# Sheet2-USB.net
KiCad netlist of a schematic drawn in Altium Designer
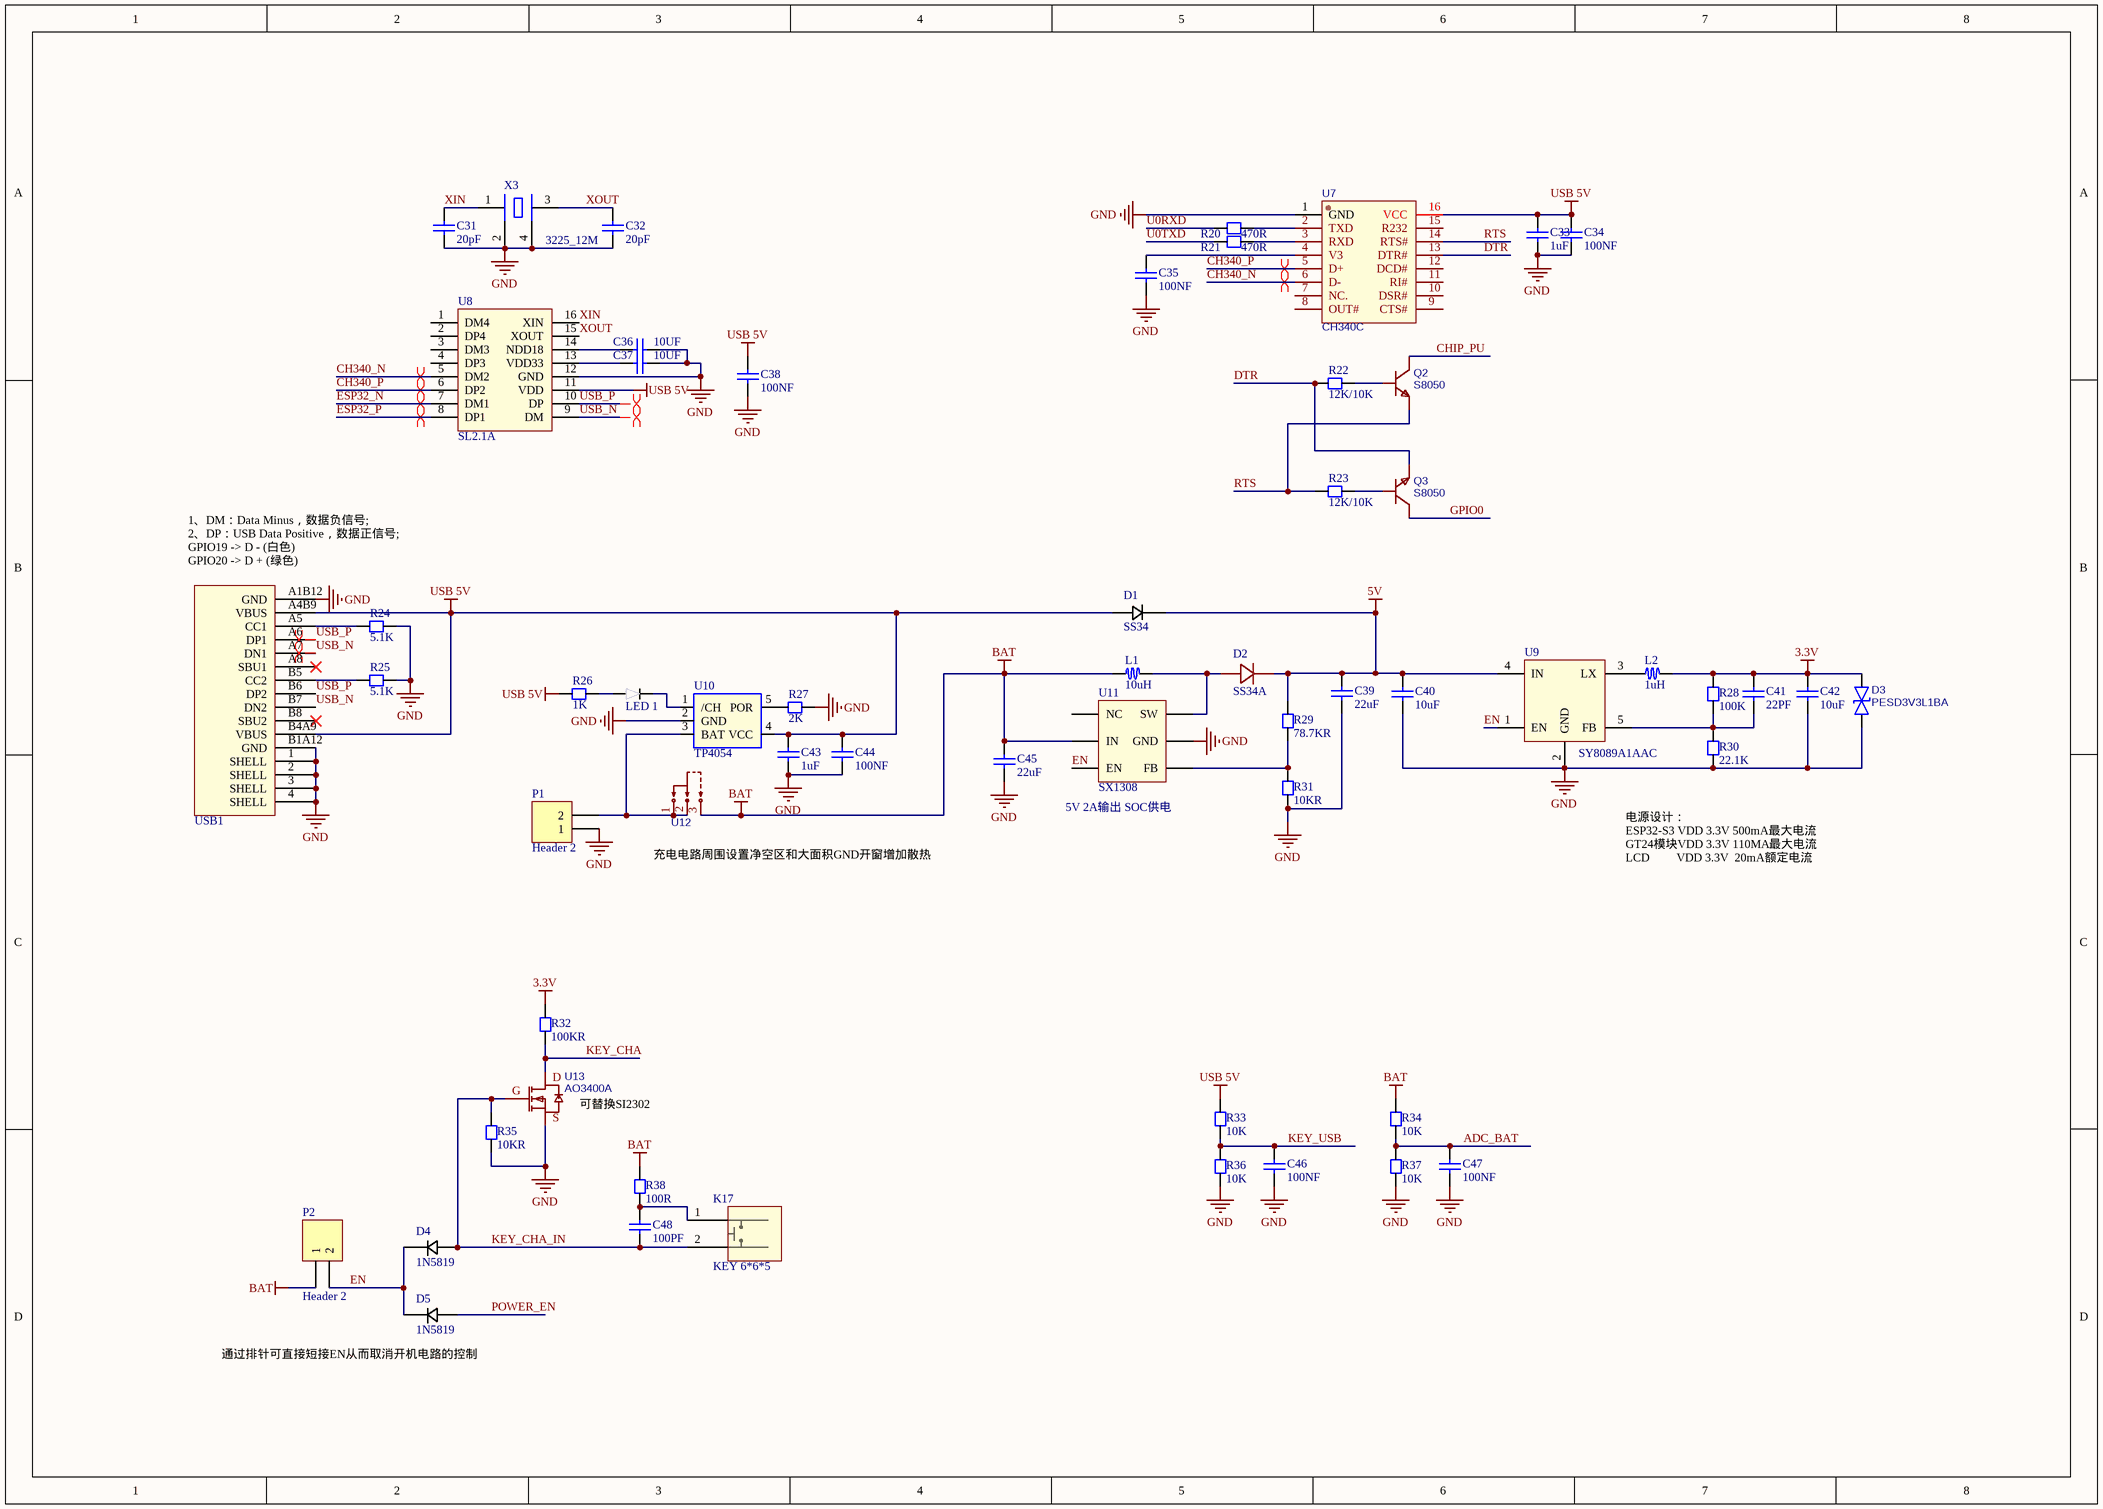
[diagram p0: Sheet2-USB.SchDoc]

(export (version "E")
  (design (tool "Eeschema 10.0.6"))
  (components
    (comp (ref "C31")
      (value "20pF")
      (footprint "CC1608-0603")
      (description "0603封装的电容")
      (fields (field (name "PUBLISHER") "Altium Limited"))
      (libsource (lib "base") (part "Cap Chip 0603"))
    )
    (comp (ref "C32")
      (value "20pF")
      (footprint "CC1608-0603")
      (description "0603封装的电容")
      (fields (field (name "PUBLISHER") "Altium Limited"))
      (libsource (lib "base") (part "Cap Chip 0603"))
    )
    (comp (ref "C33")
      (value "1uF")
      (footprint "CC1608-0603")
      (description "0603封装的电容")
      (fields (field (name "PUBLISHER") "Altium Limited"))
      (libsource (lib "base") (part "Cap Chip 0603"))
    )
    (comp (ref "C34")
      (value "100NF")
      (footprint "CC1608-0603")
      (description "0603封装的电容")
      (fields (field (name "PUBLISHER") "Altium Limited"))
      (libsource (lib "base") (part "Cap Chip 0603"))
    )
    (comp (ref "C35")
      (value "100NF")
      (footprint "CC1608-0603")
      (description "0603封装的电容")
      (fields (field (name "PUBLISHER") "Altium Limited"))
      (libsource (lib "base") (part "Cap Chip 0603"))
    )
    (comp (ref "C36")
      (value "10UF")
      (footprint "CC1608-0603")
      (description "0603封装的电容")
      (fields (field (name "PUBLISHER") "Altium Limited"))
      (libsource (lib "base") (part "Cap Chip 0603"))
    )
    (comp (ref "C37")
      (value "10UF")
      (footprint "CC1608-0603")
      (description "0603封装的电容")
      (fields (field (name "PUBLISHER") "Altium Limited"))
      (libsource (lib "base") (part "Cap Chip 0603"))
    )
    (comp (ref "C38")
      (value "100NF")
      (footprint "CC1608-0603")
      (description "0603封装的电容")
      (fields (field (name "PUBLISHER") "Altium Limited"))
      (libsource (lib "base") (part "Cap Chip 0603"))
    )
    (comp (ref "C39")
      (value "22uF")
      (footprint "CC1608-0603")
      (description "贴片电容")
      (libsource (lib "tianxiaohua_Schlib") (part "Chip capacitor"))
    )
    (comp (ref "C40")
      (value "10uF")
      (footprint "CC1608-0603")
      (description "0603封装的电容")
      (fields (field (name "PUBLISHER") "Altium Limited"))
      (libsource (lib "base") (part "Cap Chip 0603"))
    )
    (comp (ref "C41")
      (value "22PF")
      (footprint "CC1608-0603")
      (description "0603封装的电容")
      (fields (field (name "PUBLISHER") "Altium Limited"))
      (libsource (lib "base") (part "Cap Chip 0603"))
    )
    (comp (ref "C42")
      (value "10uF")
      (footprint "CC1608-0603")
      (description "0603封装的电容")
      (fields (field (name "PUBLISHER") "Altium Limited"))
      (libsource (lib "base") (part "Cap Chip 0603"))
    )
    (comp (ref "C43")
      (value "1uF")
      (footprint "CC1608-0603")
      (description "0603封装的电容")
      (fields (field (name "PUBLISHER") "Altium Limited"))
      (libsource (lib "base") (part "Cap Chip 0603"))
    )
    (comp (ref "C44")
      (value "100NF")
      (footprint "CC1608-0603")
      (description "0603封装的电容")
      (fields (field (name "PUBLISHER") "Altium Limited"))
      (libsource (lib "base") (part "Cap Chip 0603"))
    )
    (comp (ref "C45")
      (value "22uF")
      (footprint "CC1608-0603")
      (description "0603封装的电容")
      (fields (field (name "PUBLISHER") "Altium Limited"))
      (libsource (lib "base") (part "Cap Chip 0603"))
    )
    (comp (ref "C46")
      (value "100NF")
      (footprint "CC1608-0603")
      (description "0603封装的电容")
      (fields (field (name "PUBLISHER") "Altium Limited"))
      (libsource (lib "base") (part "Cap Chip 0603"))
    )
    (comp (ref "C47")
      (value "100NF")
      (footprint "CC1608-0603")
      (description "0603封装的电容")
      (fields (field (name "PUBLISHER") "Altium Limited"))
      (libsource (lib "base") (part "Cap Chip 0603"))
    )
    (comp (ref "C48")
      (value "100PF")
      (footprint "CC1608-0603")
      (description "0603封装的电容")
      (fields (field (name "PUBLISHER") "Altium Limited"))
      (libsource (lib "base") (part "Cap Chip 0603"))
    )
    (comp (ref "D1")
      (value "SS34")
      (footprint "DO-214 AA")
      (description "肖特基二极管")
      (libsource (lib "transistor") (part "SS34"))
    )
    (comp (ref "D2")
      (value "SS34A")
      (footprint "DO-214 AA SMB")
      (description "大电流肖特基二极管，5A/40V")
      (libsource (lib "tianxiaohua_Schlib") (part "SS34A"))
    )
    (comp (ref "D3")
      (value "PESD3V3L1BA")
      (footprint "SOD-323")
      (description "SOD-323 3.3V 双向ESD防静电二极管保护芯片")
      (fields (field (name "MANUFACTURER") "MDD") (field (name "MANUFACTURER PART") "SMAJ6.5CA"))
      (libsource (lib "transistor") (part "PESD3V3L1BA"))
    )
    (comp (ref "D4")
      (value "1N5819")
      (footprint "SOD-323_L1.8-W1.3-LS2.5-RD")
      (description "肖特基二极管")
      (libsource (lib "transistor") (part "1N5819"))
    )
    (comp (ref "D5")
      (value "1N5819")
      (footprint "SOD-323_L1.8-W1.3-LS2.5-RD")
      (description "肖特基二极管")
      (libsource (lib "transistor") (part "1N5819"))
    )
    (comp (ref "K17")
      (value "KEY 6*6*5")
      (footprint "KEY 6*6*5")
      (description "无声轻触开关")
      (libsource (lib "base") (part "KEY 6*6*5"))
    )
    (comp (ref "L1")
      (value "10uH")
      (footprint "Inductor-6045")
      (description "6045封装 线绕SMD功率电感")
      (libsource (lib "base") (part "Inductor-6045"))
    )
    (comp (ref "L2")
      (value "1uH")
      (footprint "Inductor-4018")
      (description "贴片电感 1206封装")
      (libsource (lib "base") (part "Inductor-4018"))
    )
    (comp (ref "LED 1") (value "LED 0603") (footprint "LED 0603") (libsource (lib "base") (part "LED 0603")))
    (comp (ref "P1")
      (value "Header 2")
      (footprint "HX2.54-2")
      (description "Header, 2-Pin")
      (fields (field (name "PUBLISHER") "Altium Limited"))
      (libsource (lib "") (part "Header 2_1"))
    )
    (comp (ref "P2")
      (value "Header 2")
      (footprint "HDR1X2")
      (description "Header, 2-Pin")
      (fields (field (name "PUBLISHER") "Altium Limited"))
      (libsource (lib "Connectors") (part "Header 2"))
    )
    (comp (ref "Q2")
      (value "S8050")
      (footprint "SOT-23")
      (fields (field (name "MANUFACTURER") "SALLTECH(萨瑞)") (field (name "CONTRIBUTOR") "lcsc"))
      (libsource (lib "transistor") (part "S8050"))
    )
    (comp (ref "Q3")
      (value "S8050")
      (footprint "SOT-23")
      (fields (field (name "MANUFACTURER") "SALLTECH(萨瑞)") (field (name "CONTRIBUTOR") "lcsc"))
      (libsource (lib "transistor") (part "S8050"))
    )
    (comp (ref "R20")
      (value "470R")
      (footprint "CR1608-0603")
      (description "0603封装电阻")
      (fields (field (name "PUBLISHER") "Altium Limited"))
      (libsource (lib "") (part "Resistor Chip 0603_1"))
    )
    (comp (ref "R21")
      (value "470R")
      (footprint "CR1608-0603")
      (description "0603封装电阻")
      (fields (field (name "PUBLISHER") "Altium Limited"))
      (libsource (lib "") (part "Resistor Chip 0603_1"))
    )
    (comp (ref "R22")
      (value "12K/10K")
      (footprint "CR1608-0603")
      (description "0603封装电阻")
      (fields (field (name "PUBLISHER") "Altium Limited"))
      (libsource (lib "") (part "Resistor Chip 0603_3"))
    )
    (comp (ref "R23")
      (value "12K/10K")
      (footprint "CR1608-0603")
      (description "0603封装电阻")
      (fields (field (name "PUBLISHER") "Altium Limited"))
      (libsource (lib "base") (part "Resistor Chip 0603"))
    )
    (comp (ref "R24")
      (value "5.1K")
      (footprint "CR1608-0603")
      (description "0603封装电阻")
      (fields (field (name "PUBLISHER") "Altium Limited"))
      (libsource (lib "") (part "Resistor Chip 0603_1"))
    )
    (comp (ref "R25")
      (value "5.1K")
      (footprint "CR1608-0603")
      (description "0603封装电阻")
      (fields (field (name "PUBLISHER") "Altium Limited"))
      (libsource (lib "") (part "Resistor Chip 0603_1"))
    )
    (comp (ref "R26")
      (value "1K")
      (footprint "CR1608-0603")
      (description "0603封装电阻")
      (fields (field (name "PUBLISHER") "Altium Limited"))
      (libsource (lib "") (part "Resistor Chip 0603_3"))
    )
    (comp (ref "R27")
      (value "2K")
      (footprint "CR1608-0603")
      (description "0603封装电阻")
      (fields (field (name "PUBLISHER") "Altium Limited"))
      (libsource (lib "") (part "Resistor Chip 0603_3"))
    )
    (comp (ref "R28")
      (value "100K")
      (footprint "CR1608-0603")
      (description "0603封装电阻")
      (fields (field (name "PUBLISHER") "Altium Limited"))
      (libsource (lib "") (part "Resistor Chip 0603_2"))
    )
    (comp (ref "R29")
      (value "78.7KR")
      (footprint "CR1608-0603")
      (description "贴片电阻")
      (libsource (lib "tianxiaohua_Schlib") (part "Chip resistor"))
    )
    (comp (ref "R30")
      (value "22.1K")
      (footprint "CR1608-0603")
      (description "0603封装电阻")
      (fields (field (name "PUBLISHER") "Altium Limited"))
      (libsource (lib "") (part "Resistor Chip 0603_2"))
    )
    (comp (ref "R31")
      (value "10KR")
      (footprint "CR1608-0603")
      (description "贴片电阻")
      (libsource (lib "tianxiaohua_Schlib") (part "Chip resistor"))
    )
    (comp (ref "R32")
      (value "100KR")
      (footprint "CR1608-0603")
      (description "贴片电阻")
      (libsource (lib "tianxiaohua_Schlib") (part "Chip resistor"))
    )
    (comp (ref "R33")
      (value "10K")
      (footprint "CR1608-0603")
      (description "0603封装电阻")
      (fields (field (name "PUBLISHER") "Altium Limited"))
      (libsource (lib "base") (part "Resistor Chip 0603"))
    )
    (comp (ref "R34")
      (value "10K")
      (footprint "CR1608-0603")
      (description "0603封装电阻")
      (fields (field (name "PUBLISHER") "Altium Limited"))
      (libsource (lib "base") (part "Resistor Chip 0603"))
    )
    (comp (ref "R35")
      (value "10KR")
      (footprint "CR1608-0603")
      (description "贴片电阻")
      (libsource (lib "tianxiaohua_Schlib") (part "Chip resistor"))
    )
    (comp (ref "R36")
      (value "10K")
      (footprint "CR1608-0603")
      (description "0603封装电阻")
      (fields (field (name "PUBLISHER") "Altium Limited"))
      (libsource (lib "base") (part "Resistor Chip 0603"))
    )
    (comp (ref "R37")
      (value "10K")
      (footprint "CR1608-0603")
      (description "0603封装电阻")
      (fields (field (name "PUBLISHER") "Altium Limited"))
      (libsource (lib "base") (part "Resistor Chip 0603"))
    )
    (comp (ref "R38")
      (value "100R")
      (footprint "CR1608-0603")
      (description "0603封装电阻")
      (fields (field (name "PUBLISHER") "Altium Limited"))
      (libsource (lib "") (part "Resistor Chip 0603_2"))
    )
    (comp (ref "U7")
      (value "CH340C")
      (footprint "SOP-16")
      (fields (field (name "MANUFACTURER") "WCH(南京沁恒)"))
      (libsource (lib "PB-Chip") (part "CH340C"))
    )
    (comp (ref "U8")
      (value "SL2.1A")
      (footprint "SOP-16")
      (description "USB HUB 四拓展")
      (libsource (lib "sensor") (part "SL2.1A"))
    )
    (comp (ref "U9")
      (value "SY8089A1AAC")
      (footprint "SOT23-5")
      (libsource (lib "power-chip") (part "SY8089A1AAC"))
    )
    (comp (ref "U10")
      (value "TP4054")
      (footprint "SOT23-5")
      (description "迷你充电IC SOT-23-5")
      (libsource (lib "power-chip") (part "TP4054"))
    )
    (comp (ref "U11")
      (value "SX1308")
      (footprint "SOT23-6")
      (description "SOT23-6 升压芯片")
      (libsource (lib "power-chip") (part "SX1308"))
    )
    (comp (ref "U12")
      (value "HX SS12D10G4")
      (footprint "SW-TH_3P-SS12D06")
      (fields (field (name "BOM_SUPPLIER PART") "C5149841") (field (name "CONTRIBUTOR") "lcsc"))
      (libsource (lib "base") (part "SW-TH_3P-SS12D06"))
    )
    (comp (ref "U13")
      (value "AO3400A")
      (footprint "SOT-23")
      (description "UMW AO3400A SOT-23 30V/5.8A N沟道 MOS(场效应管)芯片")
      (fields
        (field (name "MANUFACTURER") "ElecSuper(静芯微）")
        (field (name "MANUFACTURER PART") "AO3401A")
        (field (name "CONTRIBUTOR") "lcsc")
      )
      (libsource (lib "transistor") (part "AO3400A"))
    )
    (comp (ref "USB1")
      (value "Tpye-c 16P")
      (footprint "TYPE-C 16P")
      (description "16P 封装的TYPE -c接口 4固定插脚 双向")
      (libsource (lib "Connectors") (part "Tpye-c 16P"))
    )
    (comp (ref "X3")
      (value "3225_12M")
      (footprint "XTAL-3225")
      (description "3225封装的晶振")
      (libsource (lib "base") (part "XTAL 3225"))
    )
  )
  (nets
    (net (code "1") (name "/ADC_BAT") (class "Default")
      (node (ref "C47") (pin "2") (pinfunction "2_2") (pintype "passive"))
      (node (ref "R34") (pin "1") (pinfunction "1_1") (pintype "passive"))
      (node (ref "R37") (pin "2") (pinfunction "2_2") (pintype "passive"))
    )
    (net (code "2") (name "/CH340_N") (class "Default")
      (node (ref "U7") (pin "6") (pinfunction "D-_6") (pintype "passive"))
      (node (ref "U8") (pin "5") (pinfunction "DM2_5") (pintype "passive"))
    )
    (net (code "3") (name "/CH340_P") (class "Default")
      (node (ref "U7") (pin "5") (pinfunction "D+_5") (pintype "passive"))
      (node (ref "U8") (pin "6") (pinfunction "DP2_6") (pintype "passive"))
    )
    (net (code "4") (name "/CHIP_PU") (class "Default")
      (node (ref "Q2") (pin "3") (pinfunction "C_3") (pintype "passive"))
    )
    (net (code "5") (name "/DTR") (class "Default")
      (node (ref "Q3") (pin "2") (pinfunction "E_2") (pintype "passive"))
      (node (ref "R22") (pin "1") (pinfunction "1_1") (pintype "passive"))
      (node (ref "U7") (pin "13") (pinfunction "DTR#_13") (pintype "passive"))
    )
    (net (code "6") (name "/EN") (class "Default")
      (node (ref "D4") (pin "1") (pinfunction "1_1") (pintype "passive"))
      (node (ref "D5") (pin "1") (pinfunction "1_1") (pintype "passive"))
      (node (ref "P2") (pin "2") (pinfunction "2_2") (pintype "passive"))
      (node (ref "U11") (pin "4") (pinfunction "EN_4") (pintype "passive"))
      (node (ref "U9") (pin "1") (pinfunction "EN_1") (pintype "passive"))
    )
    (net (code "7") (name "/ESP32_N") (class "Default")
      (node (ref "U8") (pin "7") (pinfunction "DM1_7") (pintype "passive"))
    )
    (net (code "8") (name "/ESP32_P") (class "Default")
      (node (ref "U8") (pin "8") (pinfunction "DP1_8") (pintype "passive"))
    )
    (net (code "9") (name "/GPIO0") (class "Default")
      (node (ref "Q3") (pin "3") (pinfunction "C_3") (pintype "passive"))
    )
    (net (code "10") (name "/KEY_CHA") (class "Default")
      (node (ref "R32") (pin "1") (pinfunction "1_1") (pintype "passive"))
      (node (ref "U13") (pin "3") (pinfunction "D_3") (pintype "passive"))
    )
    (net (code "11") (name "/KEY_CHA_IN") (class "Default")
      (node (ref "C48") (pin "2") (pinfunction "2_2") (pintype "passive"))
      (node (ref "D4") (pin "2") (pinfunction "2_2") (pintype "passive"))
      (node (ref "K17") (pin "2") (pinfunction "2_2") (pintype "passive"))
      (node (ref "R35") (pin "2") (pinfunction "2_2") (pintype "passive"))
      (node (ref "U13") (pin "1") (pinfunction "G_1") (pintype "passive"))
    )
    (net (code "12") (name "/KEY_USB") (class "Default")
      (node (ref "C46") (pin "2") (pinfunction "2_2") (pintype "passive"))
      (node (ref "R33") (pin "1") (pinfunction "1_1") (pintype "passive"))
      (node (ref "R36") (pin "2") (pinfunction "2_2") (pintype "passive"))
    )
    (net (code "13") (name "/POWER_EN") (class "Default")
      (node (ref "D5") (pin "2") (pinfunction "2_2") (pintype "passive"))
    )
    (net (code "14") (name "/RTS") (class "Default")
      (node (ref "Q2") (pin "2") (pinfunction "E_2") (pintype "passive"))
      (node (ref "R23") (pin "1") (pinfunction "1_1") (pintype "passive"))
      (node (ref "U7") (pin "14") (pinfunction "RTS#_14") (pintype "passive"))
    )
    (net (code "15") (name "/U0RXD") (class "Default")
      (node (ref "R20") (pin "2") (pinfunction "2_2") (pintype "passive"))
    )
    (net (code "16") (name "/U0TXD") (class "Default")
      (node (ref "R21") (pin "2") (pinfunction "2_2") (pintype "passive"))
    )
    (net (code "17") (name "/USB_N") (class "Default")
      (node (ref "U8") (pin "9") (pinfunction "DM_9") (pintype "passive"))
      (node (ref "USB1") (pin "A7") (pinfunction "DN1_A7") (pintype "power_in"))
      (node (ref "USB1") (pin "B7") (pinfunction "DN2_B7") (pintype "power_in"))
    )
    (net (code "18") (name "/USB_P") (class "Default")
      (node (ref "U8") (pin "10") (pinfunction "DP_10") (pintype "passive"))
      (node (ref "USB1") (pin "A6") (pinfunction "DP1_A6") (pintype "power_in"))
      (node (ref "USB1") (pin "B6") (pinfunction "DP2_B6") (pintype "power_in"))
    )
    (net (code "19") (name "/XIN") (class "Default")
      (node (ref "C31") (pin "2") (pinfunction "2_2") (pintype "passive"))
      (node (ref "U8") (pin "16") (pinfunction "XIN_16") (pintype "passive"))
      (node (ref "X3") (pin "1") (pinfunction "OSC1_1") (pintype "passive"))
    )
    (net (code "20") (name "/XOUT") (class "Default")
      (node (ref "C32") (pin "2") (pinfunction "2_2") (pintype "passive"))
      (node (ref "U8") (pin "15") (pinfunction "XOUT_15") (pintype "passive"))
      (node (ref "X3") (pin "3") (pinfunction "OSC2_3") (pintype "passive"))
    )
    (net (code "21") (name "3.3V") (class "Default")
      (node (ref "C41") (pin "2") (pinfunction "2_2") (pintype "passive"))
      (node (ref "C42") (pin "2") (pinfunction "2_2") (pintype "passive"))
      (node (ref "D3") (pin "1") (pinfunction "1_1") (pintype "passive"))
      (node (ref "L2") (pin "2") (pinfunction "2_2") (pintype "passive"))
      (node (ref "R28") (pin "1") (pinfunction "1_1") (pintype "passive"))
      (node (ref "R32") (pin "2") (pinfunction "2_2") (pintype "passive"))
    )
    (net (code "22") (name "5V") (class "Default")
      (node (ref "C39") (pin "1") (pinfunction "1_1") (pintype "passive"))
      (node (ref "C40") (pin "2") (pinfunction "2_2") (pintype "passive"))
      (node (ref "D1") (pin "1") (pinfunction "K_1") (pintype "passive"))
      (node (ref "D2") (pin "1") (pinfunction "C_1") (pintype "passive"))
      (node (ref "R29") (pin "2") (pinfunction "2_2") (pintype "passive"))
      (node (ref "U9") (pin "4") (pinfunction "IN_4") (pintype "passive"))
    )
    (net (code "23") (name "BAT") (class "Default")
      (node (ref "C45") (pin "2") (pinfunction "2_2") (pintype "passive"))
      (node (ref "L1") (pin "1") (pinfunction "1_1") (pintype "passive"))
      (node (ref "P2") (pin "1") (pinfunction "1_1") (pintype "passive"))
      (node (ref "R34") (pin "2") (pinfunction "2_2") (pintype "passive"))
      (node (ref "R38") (pin "1") (pinfunction "1_1") (pintype "passive"))
      (node (ref "U11") (pin "5") (pinfunction "IN_5") (pintype "passive"))
      (node (ref "U12") (pin "3") (pinfunction "3_3") (pintype "passive"))
    )
    (net (code "24") (name "GND") (class "Default")
      (node (ref "C31") (pin "1") (pinfunction "1_1") (pintype "passive"))
      (node (ref "C32") (pin "1") (pinfunction "1_1") (pintype "passive"))
      (node (ref "C33") (pin "1") (pinfunction "1_1") (pintype "passive"))
      (node (ref "C34") (pin "1") (pinfunction "1_1") (pintype "passive"))
      (node (ref "C35") (pin "1") (pinfunction "1_1") (pintype "passive"))
      (node (ref "C36") (pin "1") (pinfunction "1_1") (pintype "passive"))
      (node (ref "C37") (pin "1") (pinfunction "1_1") (pintype "passive"))
      (node (ref "C38") (pin "1") (pinfunction "1_1") (pintype "passive"))
      (node (ref "C39") (pin "2") (pinfunction "2_2") (pintype "passive"))
      (node (ref "C40") (pin "1") (pinfunction "1_1") (pintype "passive"))
      (node (ref "C42") (pin "1") (pinfunction "1_1") (pintype "passive"))
      (node (ref "C43") (pin "1") (pinfunction "1_1") (pintype "passive"))
      (node (ref "C44") (pin "1") (pinfunction "1_1") (pintype "passive"))
      (node (ref "C45") (pin "1") (pinfunction "1_1") (pintype "passive"))
      (node (ref "C46") (pin "1") (pinfunction "1_1") (pintype "passive"))
      (node (ref "C47") (pin "1") (pinfunction "1_1") (pintype "passive"))
      (node (ref "D3") (pin "2") (pinfunction "2_2") (pintype "passive"))
      (node (ref "P1") (pin "1") (pinfunction "1_1") (pintype "passive"))
      (node (ref "R24") (pin "1") (pinfunction "1_1") (pintype "passive"))
      (node (ref "R25") (pin "1") (pinfunction "1_1") (pintype "passive"))
      (node (ref "R27") (pin "2") (pinfunction "2_2") (pintype "passive"))
      (node (ref "R30") (pin "2") (pinfunction "2_2") (pintype "passive"))
      (node (ref "R31") (pin "1") (pinfunction "1_1") (pintype "passive"))
      (node (ref "R35") (pin "1") (pinfunction "1_1") (pintype "passive"))
      (node (ref "R36") (pin "1") (pinfunction "1_1") (pintype "passive"))
      (node (ref "R37") (pin "1") (pinfunction "1_1") (pintype "passive"))
      (node (ref "U10") (pin "2") (pinfunction "GND_2") (pintype "passive"))
      (node (ref "U11") (pin "2") (pinfunction "GND_2") (pintype "passive"))
      (node (ref "U13") (pin "2") (pinfunction "S_2") (pintype "passive"))
      (node (ref "U7") (pin "1") (pinfunction "GND_1") (pintype "passive"))
      (node (ref "U8") (pin "12") (pinfunction "GND_12") (pintype "passive"))
      (node (ref "U9") (pin "2") (pinfunction "GND_2") (pintype "passive"))
      (node (ref "USB1") (pin "1") (pinfunction "SHELL_1") (pintype "power_in"))
      (node (ref "USB1") (pin "2") (pinfunction "SHELL_2") (pintype "power_in"))
      (node (ref "USB1") (pin "3") (pinfunction "SHELL_3") (pintype "power_in"))
      (node (ref "USB1") (pin "4") (pinfunction "SHELL_4") (pintype "power_in"))
      (node (ref "USB1") (pin "A1B12") (pinfunction "GND_A1B12") (pintype "power_in"))
      (node (ref "USB1") (pin "B1A12") (pinfunction "GND_B1A12") (pintype "power_in"))
      (node (ref "X3") (pin "2") (pinfunction "GND_2") (pintype "passive"))
      (node (ref "X3") (pin "4") (pinfunction "GND_4") (pintype "passive"))
    )
    (net (code "25") (name "Net-(C48-Pad1)") (class "Default")
      (node (ref "C48") (pin "1") (pinfunction "1_1") (pintype "passive"))
      (node (ref "K17") (pin "1") (pinfunction "1_1") (pintype "passive"))
      (node (ref "R38") (pin "2") (pinfunction "2_2") (pintype "passive"))
    )
    (net (code "26") (name "Net-(D2-A)") (class "Default")
      (node (ref "D2") (pin "2") (pinfunction "A_2") (pintype "passive"))
      (node (ref "L1") (pin "2") (pinfunction "2_2") (pintype "passive"))
      (node (ref "U11") (pin "1") (pinfunction "SW_1") (pintype "passive"))
    )
    (net (code "27") (name "Net-(LED 1-Pad1)") (class "Default")
      (node (ref "LED 1") (pin "1") (pinfunction "1_1") (pintype "passive"))
      (node (ref "R26") (pin "2") (pinfunction "2_2") (pintype "passive"))
    )
    (net (code "28") (name "Net-(Q2-B)") (class "Default")
      (node (ref "Q2") (pin "1") (pinfunction "B_1") (pintype "passive"))
      (node (ref "R22") (pin "2") (pinfunction "2_2") (pintype "passive"))
    )
    (net (code "29") (name "Net-(Q3-B)") (class "Default")
      (node (ref "Q3") (pin "1") (pinfunction "B_1") (pintype "passive"))
      (node (ref "R23") (pin "2") (pinfunction "2_2") (pintype "passive"))
    )
    (net (code "30") (name "Net-(U7-RXD)") (class "Default")
      (node (ref "R21") (pin "1") (pinfunction "1_1") (pintype "passive"))
      (node (ref "U7") (pin "3") (pinfunction "RXD_3") (pintype "passive"))
    )
    (net (code "31") (name "Net-(U7-TXD)") (class "Default")
      (node (ref "R20") (pin "1") (pinfunction "1_1") (pintype "passive"))
      (node (ref "U7") (pin "2") (pinfunction "TXD_2") (pintype "passive"))
    )
    (net (code "32") (name "Net-(U7-V3)") (class "Default")
      (node (ref "C35") (pin "2") (pinfunction "2_2") (pintype "passive"))
      (node (ref "U7") (pin "4") (pinfunction "V3_4") (pintype "passive"))
    )
    (net (code "33") (name "Net-(U8-NDD18)") (class "Default")
      (node (ref "C36") (pin "2") (pinfunction "2_2") (pintype "passive"))
      (node (ref "U8") (pin "14") (pinfunction "NDD18_14") (pintype "passive"))
    )
    (net (code "34") (name "Net-(U8-VDD33)") (class "Default")
      (node (ref "C37") (pin "2") (pinfunction "2_2") (pintype "passive"))
      (node (ref "U8") (pin "13") (pinfunction "VDD33_13") (pintype "passive"))
    )
    (net (code "35") (name "Net-(U9-FB)") (class "Default")
      (node (ref "C41") (pin "1") (pinfunction "1_1") (pintype "passive"))
      (node (ref "R28") (pin "2") (pinfunction "2_2") (pintype "passive"))
      (node (ref "R30") (pin "1") (pinfunction "1_1") (pintype "passive"))
      (node (ref "U9") (pin "5") (pinfunction "FB_5") (pintype "passive"))
    )
    (net (code "36") (name "Net-(U9-LX)") (class "Default")
      (node (ref "L2") (pin "1") (pinfunction "1_1") (pintype "passive"))
      (node (ref "U9") (pin "3") (pinfunction "LX_3") (pintype "passive"))
    )
    (net (code "37") (name "Net-(U10-BAT)") (class "Default")
      (node (ref "P1") (pin "2") (pinfunction "2_2") (pintype "passive"))
      (node (ref "U10") (pin "3") (pinfunction "BAT_3") (pintype "passive"))
      (node (ref "U12") (pin "1") (pinfunction "1_1") (pintype "passive"))
      (node (ref "U12") (pin "2") (pinfunction "2_2") (pintype "passive"))
    )
    (net (code "38") (name "Net-(U10-POR)") (class "Default")
      (node (ref "R27") (pin "1") (pinfunction "1_1") (pintype "passive"))
      (node (ref "U10") (pin "5") (pinfunction "POR_5") (pintype "passive"))
    )
    (net (code "39") (name "Net-(U10-{slash}CH)") (class "Default")
      (node (ref "LED 1") (pin "2") (pinfunction "2_2") (pintype "passive"))
      (node (ref "U10") (pin "1") (pinfunction "/CH_1") (pintype "passive"))
    )
    (net (code "40") (name "Net-(U11-FB)") (class "Default")
      (node (ref "R29") (pin "1") (pinfunction "1_1") (pintype "passive"))
      (node (ref "R31") (pin "2") (pinfunction "2_2") (pintype "passive"))
      (node (ref "U11") (pin "3") (pinfunction "FB_3") (pintype "passive"))
    )
    (net (code "41") (name "Net-(USB1-CC1)") (class "Default")
      (node (ref "R24") (pin "2") (pinfunction "2_2") (pintype "passive"))
      (node (ref "USB1") (pin "A5") (pinfunction "CC1_A5") (pintype "power_in"))
    )
    (net (code "42") (name "Net-(USB1-CC2)") (class "Default")
      (node (ref "R25") (pin "2") (pinfunction "2_2") (pintype "passive"))
      (node (ref "USB1") (pin "B5") (pinfunction "CC2_B5") (pintype "power_in"))
    )
    (net (code "43") (name "USB 5V") (class "Default")
      (node (ref "C33") (pin "2") (pinfunction "2_2") (pintype "passive"))
      (node (ref "C34") (pin "2") (pinfunction "2_2") (pintype "passive"))
      (node (ref "C38") (pin "2") (pinfunction "2_2") (pintype "passive"))
      (node (ref "C43") (pin "2") (pinfunction "2_2") (pintype "passive"))
      (node (ref "C44") (pin "2") (pinfunction "2_2") (pintype "passive"))
      (node (ref "D1") (pin "2") (pinfunction "A_2") (pintype "passive"))
      (node (ref "R26") (pin "1") (pinfunction "1_1") (pintype "passive"))
      (node (ref "R33") (pin "2") (pinfunction "2_2") (pintype "passive"))
      (node (ref "U10") (pin "4") (pinfunction "VCC_4") (pintype "passive"))
      (node (ref "U7") (pin "16") (pinfunction "VCC_16") (pintype "passive"))
      (node (ref "U8") (pin "11") (pinfunction "VDD_11") (pintype "passive"))
      (node (ref "USB1") (pin "A4B9") (pinfunction "VBUS_A4B9") (pintype "power_in"))
      (node (ref "USB1") (pin "B4A9") (pinfunction "VBUS_B4A9") (pintype "power_in"))
    )
    (net (code "44") (name "unconnected-(U7-CTS#-Pad9)") (class "Default")
      (node (ref "U7") (pin "9") (pinfunction "CTS#_9") (pintype "passive"))
    )
    (net (code "45") (name "unconnected-(U7-DCD#-Pad12)") (class "Default")
      (node (ref "U7") (pin "12") (pinfunction "DCD#_12") (pintype "passive"))
    )
    (net (code "46") (name "unconnected-(U7-DSR#-Pad10)") (class "Default")
      (node (ref "U7") (pin "10") (pinfunction "DSR#_10") (pintype "passive"))
    )
    (net (code "47") (name "unconnected-(U7-NC.-Pad7)") (class "Default")
      (node (ref "U7") (pin "7") (pinfunction "NC._7") (pintype "passive"))
    )
    (net (code "48") (name "unconnected-(U7-OUT#-Pad8)") (class "Default")
      (node (ref "U7") (pin "8") (pinfunction "OUT#_8") (pintype "passive"))
    )
    (net (code "49") (name "unconnected-(U7-R232-Pad15)") (class "Default")
      (node (ref "U7") (pin "15") (pinfunction "R232_15") (pintype "passive"))
    )
    (net (code "50") (name "unconnected-(U7-RI#-Pad11)") (class "Default")
      (node (ref "U7") (pin "11") (pinfunction "RI#_11") (pintype "passive"))
    )
    (net (code "51") (name "unconnected-(U8-DM3-Pad3)") (class "Default")
      (node (ref "U8") (pin "3") (pinfunction "DM3_3") (pintype "passive"))
    )
    (net (code "52") (name "unconnected-(U8-DM4-Pad1)") (class "Default")
      (node (ref "U8") (pin "1") (pinfunction "DM4_1") (pintype "passive"))
    )
    (net (code "53") (name "unconnected-(U8-DP3-Pad4)") (class "Default")
      (node (ref "U8") (pin "4") (pinfunction "DP3_4") (pintype "passive"))
    )
    (net (code "54") (name "unconnected-(U8-DP4-Pad2)") (class "Default")
      (node (ref "U8") (pin "2") (pinfunction "DP4_2") (pintype "passive"))
    )
    (net (code "55") (name "unconnected-(U11-NC-Pad6)") (class "Default")
      (node (ref "U11") (pin "6") (pinfunction "NC_6") (pintype "passive"))
    )
    (net (code "56") (name "unconnected-(USB1-SBU1-PadA8)") (class "Default")
      (node (ref "USB1") (pin "A8") (pinfunction "SBU1_A8") (pintype "power_in+no_connect"))
    )
    (net (code "57") (name "unconnected-(USB1-SBU2-PadB8)") (class "Default")
      (node (ref "USB1") (pin "B8") (pinfunction "SBU2_B8") (pintype "power_in+no_connect"))
    )
  )
)
